# SparkFun_Ublox_SAM-M8Q.net
KiCad netlist of a schematic drawn in EAGLE
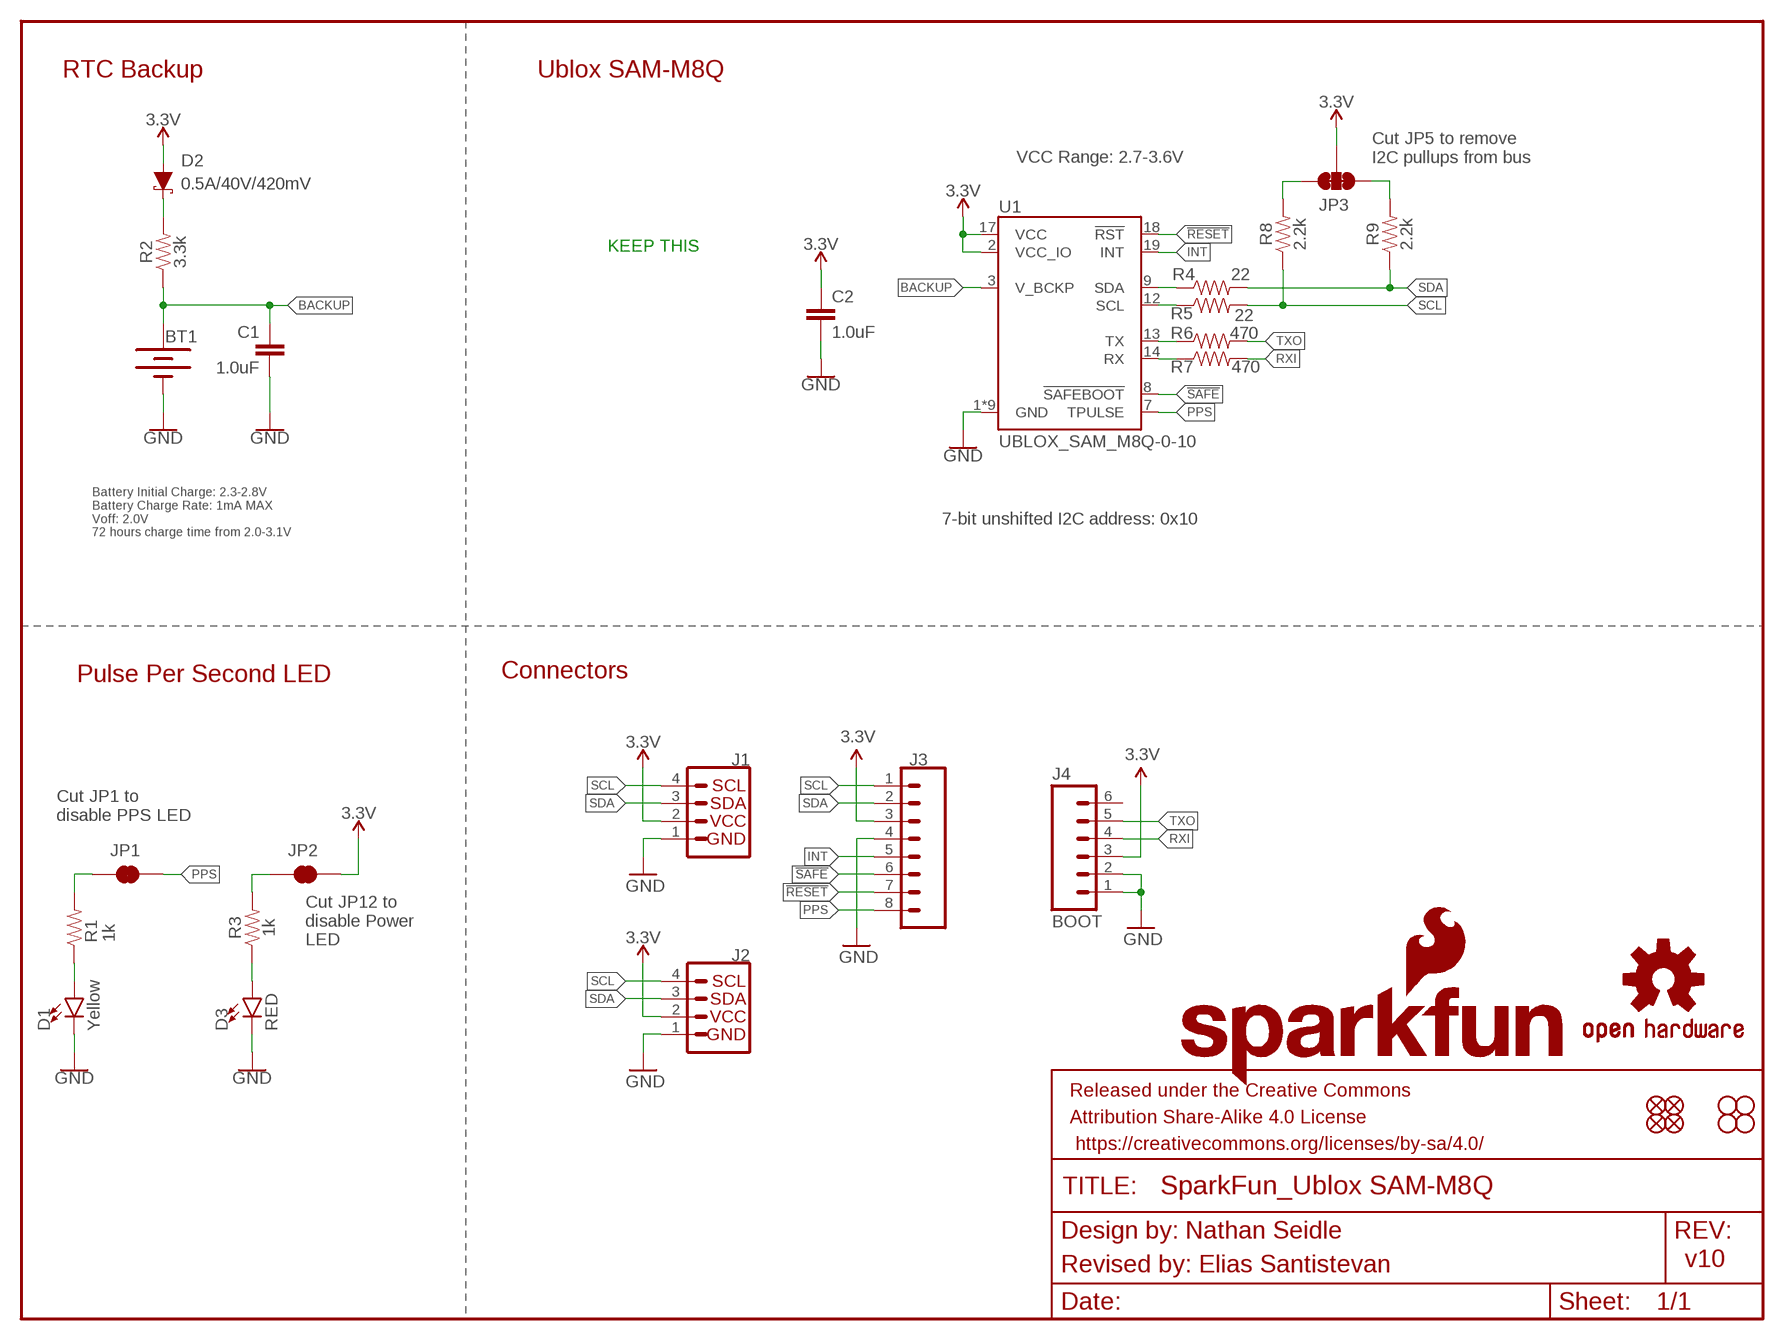
[diagram p0: schematic, sheet 1]

(export (version "E")
  (design (tool "Eeschema 10.0.6"))
  (components
    (comp (ref "BT1")
      (value "6.8MM_COIN_CELL")
      (footprint "eagle-import:ML414H_IV01E")
      (libsource (lib "eagle-import") (part "ML414H_IV01E_BATTERY"))
    )
    (comp (ref "C1")
      (value "1.0uF")
      (footprint "eagle-import:0603")
      (libsource (lib "eagle-import") (part "1.0UF-0603-16V-10%"))
    )
    (comp (ref "C2")
      (value "1.0uF")
      (footprint "eagle-import:0603")
      (libsource (lib "eagle-import") (part "1.0UF-0603-16V-10%"))
    )
    (comp (ref "D1")
      (value "Yellow")
      (footprint "eagle-import:LED-0603")
      (libsource (lib "eagle-import") (part "LED-YELLOW0603"))
    )
    (comp (ref "D2")
      (value "0.5A/40V/420mV")
      (footprint "eagle-import:SOD-323")
      (libsource (lib "eagle-import") (part "DIODE-SCHOTTKY-PMEG4005EJ"))
    )
    (comp (ref "D3")
      (value "RED")
      (footprint "eagle-import:LED-0603")
      (libsource (lib "eagle-import") (part "LED-RED0603"))
    )
    (comp (ref "FD1")
      (value "FIDUCIALUFIDUCIAL")
      (footprint "eagle-import:FIDUCIAL-MICRO")
      (libsource (lib "eagle-import") (part "FIDUCIALUFIDUCIAL"))
    )
    (comp (ref "FD2")
      (value "FIDUCIALUFIDUCIAL")
      (footprint "eagle-import:FIDUCIAL-MICRO")
      (libsource (lib "eagle-import") (part "FIDUCIALUFIDUCIAL"))
    )
    (comp (ref "FD3")
      (value "FIDUCIALUFIDUCIAL")
      (footprint "eagle-import:FIDUCIAL-MICRO")
      (libsource (lib "eagle-import") (part "FIDUCIALUFIDUCIAL"))
    )
    (comp (ref "FD4")
      (value "FIDUCIALUFIDUCIAL")
      (footprint "eagle-import:FIDUCIAL-MICRO")
      (libsource (lib "eagle-import") (part "FIDUCIALUFIDUCIAL"))
    )
    (comp (ref "FRAME1")
      (value "FRAME-LETTER")
      (footprint "eagle-import:CREATIVE_COMMONS")
      (libsource (lib "eagle-import") (part "FRAME-LETTER"))
    )
    (comp (ref "H1")
      (value "STAND-OFF")
      (footprint "eagle-import:STAND-OFF")
      (libsource (lib "eagle-import") (part "STAND-OFF"))
    )
    (comp (ref "H2")
      (value "STAND-OFF")
      (footprint "eagle-import:STAND-OFF")
      (libsource (lib "eagle-import") (part "STAND-OFF"))
    )
    (comp (ref "H3")
      (value "STAND-OFF")
      (footprint "eagle-import:STAND-OFF")
      (libsource (lib "eagle-import") (part "STAND-OFF"))
    )
    (comp (ref "H4")
      (value "STAND-OFF")
      (footprint "eagle-import:STAND-OFF")
      (libsource (lib "eagle-import") (part "STAND-OFF"))
    )
    (comp (ref "J1")
      (value "Qwiic Right Angle")
      (footprint "eagle-import:JST04_1MM_RA")
      (libsource (lib "eagle-import") (part "I2C_STANDARDQWIIC"))
    )
    (comp (ref "J2")
      (value "Qwiic Right Angle")
      (footprint "eagle-import:JST04_1MM_RA")
      (libsource (lib "eagle-import") (part "I2C_STANDARDQWIIC"))
    )
    (comp (ref "J3")
      (value "CONN_08NO_SILK_FEMALE_PTH")
      (footprint "eagle-import:1X08_NO_SILK")
      (libsource (lib "eagle-import") (part "CONN_08NO_SILK_FEMALE_PTH"))
    )
    (comp (ref "J4")
      (value "BOOT")
      (footprint "eagle-import:1X06_NO_SILK")
      (libsource (lib "eagle-import") (part "CONN_06NO_SILK_NO_POP"))
    )
    (comp (ref "JP1")
      (value "JUMPER-SMT_2_NC_TRACE_SILK")
      (footprint "eagle-import:SMT-JUMPER_2_NC_TRACE_SILK")
      (libsource (lib "eagle-import") (part "JUMPER-SMT_2_NC_TRACE_SILK"))
    )
    (comp (ref "JP2")
      (value "JUMPER-SMT_2_NC_TRACE_SILK")
      (footprint "eagle-import:SMT-JUMPER_2_NC_TRACE_SILK")
      (libsource (lib "eagle-import") (part "JUMPER-SMT_2_NC_TRACE_SILK"))
    )
    (comp (ref "JP3")
      (value "JUMPER-SMT_3_2-NC_TRACE_SILK")
      (footprint "eagle-import:SMT-JUMPER_3_2-NC_TRACE_SILK")
      (libsource (lib "eagle-import") (part "JUMPER-SMT_3_2-NC_TRACE_SILK"))
    )
    (comp (ref "LOGO1")
      (value "SFE_LOGO_NAME_FLAME.2_INCH")
      (footprint "eagle-import:SFE_LOGO_NAME_FLAME_.2")
      (libsource (lib "eagle-import") (part "SFE_LOGO_NAME_FLAME.2_INCH"))
    )
    (comp (ref "LOGO2")
      (value "OSHW-LOGOM")
      (footprint "eagle-import:OSHW-LOGO-M")
      (libsource (lib "eagle-import") (part "OSHW-LOGOM"))
    )
    (comp (ref "R1")
      (value "1k")
      (footprint "eagle-import:0603")
      (libsource (lib "eagle-import") (part "1KOHM-0603-1/10W-1%"))
    )
    (comp (ref "R2")
      (value "3.3k")
      (footprint "eagle-import:0603")
      (libsource (lib "eagle-import") (part "3.3KOHM-0603-1/10W-1%"))
    )
    (comp (ref "R3")
      (value "1k")
      (footprint "eagle-import:0603")
      (libsource (lib "eagle-import") (part "1KOHM-0603-1/10W-1%"))
    )
    (comp (ref "R4")
      (value "22")
      (footprint "eagle-import:0603")
      (libsource (lib "eagle-import") (part "22OHM-0603-1/10W-1%"))
    )
    (comp (ref "R5")
      (value "22")
      (footprint "eagle-import:0603")
      (libsource (lib "eagle-import") (part "22OHM-0603-1/10W-1%"))
    )
    (comp (ref "R6")
      (value "470")
      (footprint "eagle-import:0603")
      (libsource (lib "eagle-import") (part "470OHM-0603-1/10W-1%"))
    )
    (comp (ref "R7")
      (value "470")
      (footprint "eagle-import:0603")
      (libsource (lib "eagle-import") (part "470OHM-0603-1/10W-1%"))
    )
    (comp (ref "R8")
      (value "2.2k")
      (footprint "eagle-import:0603")
      (libsource (lib "eagle-import") (part "2.2KOHM-0603-1/10W-1%"))
    )
    (comp (ref "R9")
      (value "2.2k")
      (footprint "eagle-import:0603")
      (libsource (lib "eagle-import") (part "2.2KOHM-0603-1/10W-1%"))
    )
    (comp (ref "U1")
      (value "UBLOX_SAM_M8Q-0-10")
      (footprint "eagle-import:SAM-M8Q")
      (libsource (lib "eagle-import") (part "UBLOX_SAM_M8Q-0-10"))
    )
  )
  (nets
    (net (code "1") (name "/~{RESET}") (class "Default")
      (node (ref "J3") (pin "7") (pinfunction "7_7") (pintype "passive"))
      (node (ref "U1") (pin "18") (pinfunction "~{RST}_18") (pintype "bidirectional"))
    )
    (net (code "2") (name "/~{SAFE}") (class "Default")
      (node (ref "J3") (pin "6") (pinfunction "6_6") (pintype "passive"))
      (node (ref "U1") (pin "8") (pinfunction "~{SAFEBOOT}_8") (pintype "bidirectional"))
    )
    (net (code "3") (name "3.3V") (class "Default")
      (node (ref "C2") (pin "1") (pinfunction "1_1") (pintype "passive"))
      (node (ref "D2") (pin "A") (pinfunction "A_A") (pintype "passive"))
      (node (ref "J1") (pin "2") (pinfunction "2_2") (pintype "power_in"))
      (node (ref "J2") (pin "2") (pinfunction "2_2") (pintype "power_in"))
      (node (ref "J3") (pin "3") (pinfunction "3_3") (pintype "passive"))
      (node (ref "J4") (pin "3") (pinfunction "3_3") (pintype "passive"))
      (node (ref "JP2") (pin "2") (pinfunction "2_2") (pintype "passive"))
      (node (ref "JP3") (pin "2") (pinfunction "2_2") (pintype "passive"))
      (node (ref "U1") (pin "17") (pinfunction "VCC_17") (pintype "bidirectional"))
      (node (ref "U1") (pin "2") (pinfunction "VCC_IO_2") (pintype "bidirectional"))
    )
    (net (code "4") (name "BACKUP") (class "Default")
      (node (ref "BT1") (pin "+") (pinfunction "+_+") (pintype "power_in"))
      (node (ref "C1") (pin "1") (pinfunction "1_1") (pintype "passive"))
      (node (ref "R2") (pin "1") (pinfunction "1_1") (pintype "passive"))
      (node (ref "U1") (pin "3") (pinfunction "V_BCKP_3") (pintype "bidirectional"))
    )
    (net (code "5") (name "GND") (class "Default")
      (node (ref "BT1") (pin "-") (pinfunction "-_-") (pintype "power_in"))
      (node (ref "C1") (pin "2") (pinfunction "2_2") (pintype "passive"))
      (node (ref "C2") (pin "2") (pinfunction "2_2") (pintype "passive"))
      (node (ref "D1") (pin "C") (pinfunction "C_C") (pintype "passive"))
      (node (ref "D3") (pin "C") (pinfunction "C_C") (pintype "passive"))
      (node (ref "J1") (pin "1") (pinfunction "1_1") (pintype "power_in"))
      (node (ref "J2") (pin "1") (pinfunction "1_1") (pintype "power_in"))
      (node (ref "J3") (pin "4") (pinfunction "4_4") (pintype "passive"))
      (node (ref "J4") (pin "1") (pinfunction "1_1") (pintype "passive"))
      (node (ref "J4") (pin "2") (pinfunction "2_2") (pintype "passive"))
      (node (ref "U1") (pin "1") (pinfunction "GND_1") (pintype "bidirectional"))
      (node (ref "U1") (pin "10") (pinfunction "GND_10") (pintype "bidirectional"))
      (node (ref "U1") (pin "11") (pinfunction "GND_11") (pintype "bidirectional"))
      (node (ref "U1") (pin "15") (pinfunction "GND_15") (pintype "bidirectional"))
      (node (ref "U1") (pin "16") (pinfunction "GND_16") (pintype "bidirectional"))
      (node (ref "U1") (pin "20") (pinfunction "GND_20") (pintype "bidirectional"))
      (node (ref "U1") (pin "4") (pinfunction "GND_4") (pintype "bidirectional"))
      (node (ref "U1") (pin "5") (pinfunction "GND_5") (pintype "bidirectional"))
      (node (ref "U1") (pin "6") (pinfunction "GND_6") (pintype "bidirectional"))
    )
    (net (code "6") (name "INT") (class "Default")
      (node (ref "J3") (pin "5") (pinfunction "5_5") (pintype "passive"))
      (node (ref "U1") (pin "19") (pinfunction "INT_19") (pintype "bidirectional"))
    )
    (net (code "7") (name "Net-(D1-PadA)") (class "Default")
      (node (ref "D1") (pin "A") (pinfunction "A_A") (pintype "passive"))
      (node (ref "R1") (pin "1") (pinfunction "1_1") (pintype "passive"))
    )
    (net (code "8") (name "Net-(D2-PadC)") (class "Default")
      (node (ref "D2") (pin "C") (pinfunction "C_C") (pintype "passive"))
      (node (ref "R2") (pin "2") (pinfunction "2_2") (pintype "passive"))
    )
    (net (code "9") (name "Net-(D3-PadA)") (class "Default")
      (node (ref "D3") (pin "A") (pinfunction "A_A") (pintype "passive"))
      (node (ref "R3") (pin "1") (pinfunction "1_1") (pintype "passive"))
    )
    (net (code "10") (name "Net-(JP1-Pad1)") (class "Default")
      (node (ref "JP1") (pin "1") (pinfunction "1_1") (pintype "passive"))
      (node (ref "R1") (pin "2") (pinfunction "2_2") (pintype "passive"))
    )
    (net (code "11") (name "Net-(JP2-Pad1)") (class "Default")
      (node (ref "JP2") (pin "1") (pinfunction "1_1") (pintype "passive"))
      (node (ref "R3") (pin "2") (pinfunction "2_2") (pintype "passive"))
    )
    (net (code "12") (name "Net-(JP3-Pad1)") (class "Default")
      (node (ref "JP3") (pin "1") (pinfunction "1_1") (pintype "passive"))
      (node (ref "R9") (pin "2") (pinfunction "2_2") (pintype "passive"))
    )
    (net (code "13") (name "Net-(JP3-Pad3)") (class "Default")
      (node (ref "JP3") (pin "3") (pinfunction "3_3") (pintype "passive"))
      (node (ref "R8") (pin "2") (pinfunction "2_2") (pintype "passive"))
    )
    (net (code "14") (name "Net-(U1-RX)") (class "Default")
      (node (ref "R7") (pin "1") (pinfunction "1_1") (pintype "passive"))
      (node (ref "U1") (pin "14") (pinfunction "RX_14") (pintype "bidirectional"))
    )
    (net (code "15") (name "Net-(U1-SCL)") (class "Default")
      (node (ref "R5") (pin "1") (pinfunction "1_1") (pintype "passive"))
      (node (ref "U1") (pin "12") (pinfunction "SCL_12") (pintype "bidirectional"))
    )
    (net (code "16") (name "Net-(U1-SDA)") (class "Default")
      (node (ref "R4") (pin "1") (pinfunction "1_1") (pintype "passive"))
      (node (ref "U1") (pin "9") (pinfunction "SDA_9") (pintype "bidirectional"))
    )
    (net (code "17") (name "Net-(U1-TX)") (class "Default")
      (node (ref "R6") (pin "1") (pinfunction "1_1") (pintype "passive"))
      (node (ref "U1") (pin "13") (pinfunction "TX_13") (pintype "bidirectional"))
    )
    (net (code "18") (name "PPS") (class "Default")
      (node (ref "J3") (pin "8") (pinfunction "8_8") (pintype "passive"))
      (node (ref "JP1") (pin "2") (pinfunction "2_2") (pintype "passive"))
      (node (ref "U1") (pin "7") (pinfunction "TPULSE_7") (pintype "bidirectional"))
    )
    (net (code "19") (name "RXI") (class "Default")
      (node (ref "J4") (pin "4") (pinfunction "4_4") (pintype "passive"))
      (node (ref "R7") (pin "2") (pinfunction "2_2") (pintype "passive"))
    )
    (net (code "20") (name "SCL") (class "Default")
      (node (ref "J1") (pin "4") (pinfunction "4_4") (pintype "passive"))
      (node (ref "J2") (pin "4") (pinfunction "4_4") (pintype "passive"))
      (node (ref "J3") (pin "1") (pinfunction "1_1") (pintype "passive"))
      (node (ref "R5") (pin "2") (pinfunction "2_2") (pintype "passive"))
      (node (ref "R8") (pin "1") (pinfunction "1_1") (pintype "passive"))
    )
    (net (code "21") (name "SDA") (class "Default")
      (node (ref "J1") (pin "3") (pinfunction "3_3") (pintype "passive"))
      (node (ref "J2") (pin "3") (pinfunction "3_3") (pintype "passive"))
      (node (ref "J3") (pin "2") (pinfunction "2_2") (pintype "passive"))
      (node (ref "R4") (pin "2") (pinfunction "2_2") (pintype "passive"))
      (node (ref "R9") (pin "1") (pinfunction "1_1") (pintype "passive"))
    )
    (net (code "22") (name "TXO") (class "Default")
      (node (ref "J4") (pin "5") (pinfunction "5_5") (pintype "passive"))
      (node (ref "R6") (pin "2") (pinfunction "2_2") (pintype "passive"))
    )
    (net (code "23") (name "unconnected-(J4-Pad6)") (class "Default")
      (node (ref "J4") (pin "6") (pinfunction "6_6") (pintype "passive"))
    )
  )
)
